# temp_measure.net
KiCad netlist of a schematic drawn in Altium Designer
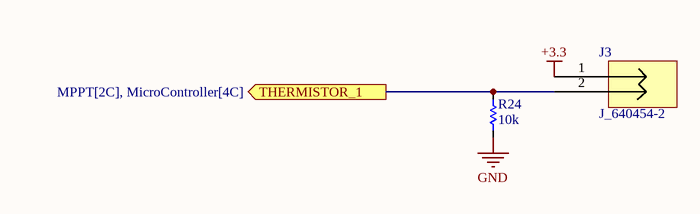
[diagram p0: temp_measure.SchDoc]

(export (version "E")
  (design (tool "Eeschema 10.0.6"))
  (components
    (comp (ref "J3")
      (value "J_640454-2")
      (footprint "640454-2")
      (description "2 Positions Header, Unshrouded Connector 0.100\" (2.54mm) Through Hole Tin")
      (libsource (lib "") (part "Symbol_1"))
    )
    (comp (ref "R24")
      (value "10k")
      (footprint "0603_RESISTOR")
      (description "RES 10K OHM 1/16W 1% 0603 SMD")
      (fields (field (name "POWER") "62.5mW") (field (name "TOLERANCE") "1%"))
      (libsource (lib "University of Minnesota - Solar Vehicle Project") (part "Symbol"))
    )
  )
  (nets
    (net (code "1") (name "+3.3") (class "Default")
      (node (ref "J3") (pin "1") (pinfunction "1_1") (pintype "passive"))
    )
    (net (code "2") (name "/THERMISTOR_1") (class "Default")
      (node (ref "J3") (pin "2") (pinfunction "2_2") (pintype "passive"))
      (node (ref "R24") (pin "2") (pinfunction "2_2") (pintype "passive"))
    )
    (net (code "3") (name "GND") (class "Default")
      (node (ref "R24") (pin "1") (pinfunction "1_1") (pintype "passive"))
    )
  )
)
